# ControlUnit.net
KiCad netlist of a schematic drawn in Altium Designer
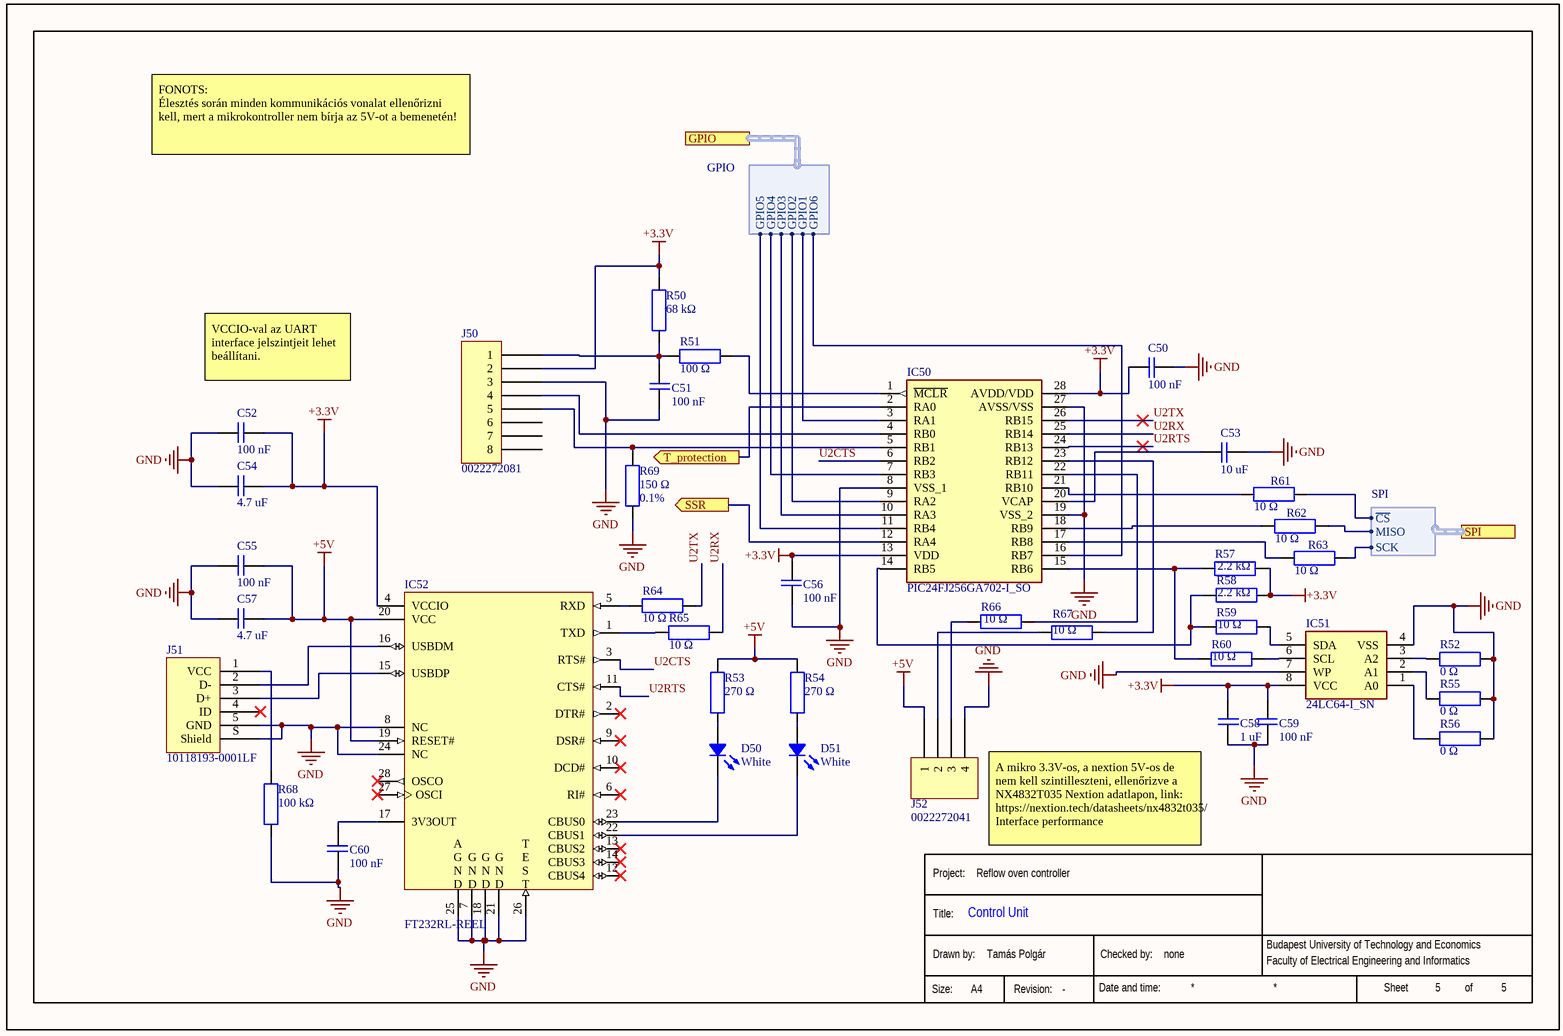
[diagram p0: ControlUnit.SchDoc]

(export (version "E")
  (design (tool "Eeschema 10.0.6"))
  (components
    (comp (ref "C50")
      (value "100 nF")
      (footprint "1206 MLCC")
      (description "Generic MLCC")
      (libsource (lib "passives") (part "Capacitor"))
    )
    (comp (ref "C51")
      (value "100 nF")
      (footprint "1206 MLCC")
      (description "Generic MLCC")
      (libsource (lib "passives") (part "Capacitor"))
    )
    (comp (ref "C52")
      (value "100 nF")
      (footprint "1206 MLCC")
      (description "Generic MLCC")
      (libsource (lib "passives") (part "Capacitor"))
    )
    (comp (ref "C53")
      (value "10 uF")
      (footprint "1210 MLCC")
      (description "Generic MLCC")
      (libsource (lib "passives") (part "Capacitor"))
    )
    (comp (ref "C54")
      (value "4.7 uF")
      (footprint "1206 MLCC")
      (description "Generic MLCC")
      (libsource (lib "passives") (part "Capacitor"))
    )
    (comp (ref "C55")
      (value "100 nF")
      (footprint "1206 MLCC")
      (description "Generic MLCC")
      (libsource (lib "passives") (part "Capacitor"))
    )
    (comp (ref "C56")
      (value "100 nF")
      (footprint "1206 MLCC")
      (description "Generic MLCC")
      (libsource (lib "passives") (part "Capacitor"))
    )
    (comp (ref "C57")
      (value "4.7 uF")
      (footprint "1206 MLCC")
      (description "Generic MLCC")
      (libsource (lib "passives") (part "Capacitor"))
    )
    (comp (ref "C58")
      (value "1 uF")
      (footprint "1206 MLCC")
      (description "Generic MLCC")
      (libsource (lib "passives") (part "Capacitor"))
    )
    (comp (ref "C59")
      (value "100 nF")
      (footprint "1206 MLCC")
      (description "Generic MLCC")
      (libsource (lib "passives") (part "Capacitor"))
    )
    (comp (ref "C60")
      (value "100 nF")
      (footprint "1206 MLCC")
      (description "Generic MLCC")
      (libsource (lib "passives") (part "Capacitor"))
    )
    (comp (ref "D50")
      (value "White")
      (footprint "LED 1206_3216")
      (description "LED WHITE 1206 SMD")
      (fields (field (name "PART NUMBER") "LTW-C230DS") (field (name "MANUFACTURER") "Lite-On Inc."))
      (libsource (lib "Celestial Altium Library - altium_library") (part "LED"))
    )
    (comp (ref "D51")
      (value "White")
      (footprint "LED 1206_3216")
      (description "LED WHITE 1206 SMD")
      (fields (field (name "PART NUMBER") "LTW-C230DS") (field (name "MANUFACTURER") "Lite-On Inc."))
      (libsource (lib "Celestial Altium Library - altium_library") (part "LED"))
    )
    (comp (ref "IC50")
      (value "PIC24FJ256GA702-I_SO")
      (footprint "SamacSys:SOIC127P1030X265-28N")
      (description "Integrated Circuit")
      (fields
        (field (name "MANUFACTURER_PART_NUMBER") "PIC24FJ256GA702-I/SO")
        (field (name "MOUSER PART NUMBER") "579-24FJ256GA702ISO")
      )
      (libsource (lib "*") (part "PIC24FJ256GA702-I_SO"))
    )
    (comp (ref "IC51")
      (value "24LC64-I_SN")
      (footprint "SamacSys:SOIC127P600X175-8N")
      (description "Integrated Circuit")
      (fields
        (field (name "MANUFACTURER_PART_NUMBER") "24LC64-I/SN")
        (field (name "MOUSER PART NUMBER") "579-24LC64-I/SN")
      )
      (libsource (lib "*") (part "24LC64-I_SN"))
    )
    (comp (ref "IC52")
      (value "FT232RL-REEL")
      (footprint "FTDI-SSOP-28_N")
      (description "USB UART IC, -0.5 to 6 V, 24 mA, -40 to 85 degC, 28-Pin SSOP, RoHS, Tape and Reel")
      (fields (field (name "MANUFACTURER") "Future Technology Devices International (FTDI)"))
      (libsource (lib "Budapest University of Technology and Economics") (part "FTDI-FT232-SSOP-28"))
    )
    (comp (ref "J50")
      (value "0022272081")
      (footprint "MOLEX KK 0022272081")
      (description "CONN HEADER VERT 8POS 2.54MM")
      (fields (field (name "MANUFACTURER") "Molex"))
      (libsource (lib "Celestial Altium Library - altium_library") (part "8 Pin"))
    )
    (comp (ref "J51")
      (value "10118193-0001LF")
      (footprint "FCI USB 10118193-0001LF")
      (description "CONN RCPT USB2.0 MICRO B SMD R/A")
      (fields (field (name "MANUFACTURER") "Amphenol ICC (FCI)"))
      (libsource (lib "Celestial Altium Library - altium_library") (part "USB 2.0 Type B Micro"))
    )
    (comp (ref "J52")
      (value "0022272041")
      (footprint "MOLEX KK 0022272041")
      (description "CONN HEADER VERT 4POS 2.54MM")
      (fields (field (name "MANUFACTURER") "Molex"))
      (libsource (lib "Celestial Altium Library - altium_library") (part "4 Pin"))
    )
    (comp (ref "R50")
      (value "68 kΩ")
      (footprint "1206 RES")
      (description "Generic SMD resistor")
      (libsource (lib "") (part "Resitor_1"))
    )
    (comp (ref "R51")
      (value "100 Ω")
      (footprint "1206 RES")
      (description "Generic SMD resistor")
      (libsource (lib "passives") (part "Resitor"))
    )
    (comp (ref "R52")
      (value "0 Ω")
      (footprint "1206 RES")
      (description "Generic SMD resistor")
      (libsource (lib "passives") (part "Resitor"))
    )
    (comp (ref "R53")
      (value "270 Ω")
      (footprint "1206 RES")
      (description "Generic SMD resistor")
      (libsource (lib "") (part "Resitor_1"))
    )
    (comp (ref "R54")
      (value "270 Ω")
      (footprint "1206 RES")
      (description "Generic SMD resistor")
      (libsource (lib "") (part "Resitor_2"))
    )
    (comp (ref "R55")
      (value "0 Ω")
      (footprint "1206 RES")
      (description "Generic SMD resistor")
      (libsource (lib "passives") (part "Resitor"))
    )
    (comp (ref "R56")
      (value "0 Ω")
      (footprint "1206 RES")
      (description "Generic SMD resistor")
      (libsource (lib "passives") (part "Resitor"))
    )
    (comp (ref "R57")
      (value "2.2 kΩ")
      (footprint "1206 RES")
      (description "Generic SMD resistor")
      (libsource (lib "passives") (part "Resitor"))
    )
    (comp (ref "R58")
      (value "2.2 kΩ")
      (footprint "1206 RES")
      (description "Generic SMD resistor")
      (libsource (lib "passives") (part "Resitor"))
    )
    (comp (ref "R59")
      (value "10 Ω")
      (footprint "1206 RES")
      (description "Generic SMD resistor")
      (libsource (lib "passives") (part "Resitor"))
    )
    (comp (ref "R60")
      (value "10 Ω")
      (footprint "1206 RES")
      (description "Generic SMD resistor")
      (libsource (lib "passives") (part "Resitor"))
    )
    (comp (ref "R61")
      (value "10 Ω")
      (footprint "1206 RES")
      (description "Generic SMD resistor")
      (libsource (lib "passives") (part "Resitor"))
    )
    (comp (ref "R62")
      (value "10 Ω")
      (footprint "1206 RES")
      (description "Generic SMD resistor")
      (libsource (lib "passives") (part "Resitor"))
    )
    (comp (ref "R63")
      (value "10 Ω")
      (footprint "1206 RES")
      (description "Generic SMD resistor")
      (libsource (lib "passives") (part "Resitor"))
    )
    (comp (ref "R64")
      (value "10 Ω")
      (footprint "1206 RES")
      (description "Generic SMD resistor")
      (libsource (lib "passives") (part "Resitor"))
    )
    (comp (ref "R65")
      (value "10 Ω")
      (footprint "1206 RES")
      (description "Generic SMD resistor")
      (libsource (lib "passives") (part "Resitor"))
    )
    (comp (ref "R66")
      (value "10 Ω")
      (footprint "1206 RES")
      (description "Generic SMD resistor")
      (libsource (lib "passives") (part "Resitor"))
    )
    (comp (ref "R67")
      (value "10 Ω")
      (footprint "1206 RES")
      (description "Generic SMD resistor")
      (libsource (lib "passives") (part "Resitor"))
    )
    (comp (ref "R68")
      (value "100 kΩ")
      (footprint "0805 RES")
      (description "Generic SMD resistor")
      (libsource (lib "") (part "Resitor_1"))
    )
    (comp (ref "R69")
      (value "150 Ω")
      (footprint "1206 RES")
      (description "Precision SMD resistor")
      (fields (field (name "TPYE") "0.1%"))
      (libsource (lib "") (part "Resitor_1"))
    )
  )
  (nets
    (net (code "3") (name "+3.3V") (class "Default")
      (node (ref "C50") (pin "2") (pintype "passive"))
      (node (ref "C52") (pin "2") (pintype "passive"))
      (node (ref "C54") (pin "2") (pintype "passive"))
      (node (ref "C56") (pin "2") (pintype "passive"))
      (node (ref "C58") (pin "1") (pintype "passive"))
      (node (ref "C59") (pin "2") (pintype "passive"))
      (node (ref "IC50") (pin "13") (pinfunction "VDD_13") (pintype "passive"))
      (node (ref "IC50") (pin "28") (pinfunction "AVDD/VDD_28") (pintype "passive"))
      (node (ref "IC51") (pin "8") (pinfunction "VCC_8") (pintype "passive"))
      (node (ref "IC52") (pin "4") (pinfunction "VCCIO_4") (pintype "power_in"))
      (node (ref "J50") (pin "2") (pinfunction "2_2") (pintype "passive"))
      (node (ref "R50") (pin "1") (pintype "passive"))
      (node (ref "R57") (pin "1") (pintype "passive"))
      (node (ref "R58") (pin "1") (pintype "passive"))
    )
    (net (code "4") (name "+5V") (class "Default")
      (node (ref "C55") (pin "2") (pintype "passive"))
      (node (ref "C57") (pin "2") (pintype "passive"))
      (node (ref "IC52") (pin "19") (pinfunction "RESET#_19") (pintype "input"))
      (node (ref "IC52") (pin "20") (pinfunction "VCC_20") (pintype "power_in"))
      (node (ref "J52") (pin "1") (pinfunction "1_1") (pintype "passive"))
      (node (ref "R53") (pin "1") (pintype "passive"))
      (node (ref "R54") (pin "2") (pintype "passive"))
    )
    (net (code "5") (name "/GPIO1") (class "Default")
      (node (ref "IC50") (pin "3") (pinfunction "RA1_3") (pintype "passive"))
    )
    (net (code "6") (name "/GPIO2") (class "Default")
      (node (ref "IC50") (pin "9") (pinfunction "RA2_9") (pintype "passive"))
    )
    (net (code "7") (name "/GPIO3") (class "Default")
      (node (ref "IC50") (pin "10") (pinfunction "RA3_10") (pintype "passive"))
    )
    (net (code "8") (name "/GPIO4") (class "Default")
      (node (ref "IC50") (pin "7") (pinfunction "RB3_7") (pintype "passive"))
    )
    (net (code "9") (name "/GPIO5") (class "Default")
      (node (ref "IC50") (pin "11") (pinfunction "RB4_11") (pintype "passive"))
    )
    (net (code "10") (name "/GPIO6") (class "Default")
      (node (ref "IC50") (pin "16") (pinfunction "RB7_16") (pintype "passive"))
    )
    (net (code "11") (name "/MISO") (class "Default") (node (ref "R62") (pin "1") (pintype "passive")))
    (net (code "12") (name "/SCK") (class "Default") (node (ref "R63") (pin "1") (pintype "passive")))
    (net (code "13") (name "/SSR") (class "Default")
      (node (ref "IC50") (pin "12") (pinfunction "RA4_12") (pintype "passive"))
    )
    (net (code "14") (name "/T_protection") (class "Default")
      (node (ref "IC50") (pin "2") (pinfunction "RA0_2") (pintype "passive"))
    )
    (net (code "15") (name "/U2CTS") (class "Default")
      (node (ref "IC50") (pin "6") (pinfunction "RB2_6") (pintype "passive"))
      (node (ref "IC52") (pin "3") (pinfunction "RTS#_3") (pintype "output"))
    )
    (net (code "16") (name "/U2RTS") (class "Default")
      (node (ref "IC50") (pin "24") (pinfunction "RB13_24") (pintype "passive"))
      (node (ref "IC52") (pin "11") (pinfunction "CTS#_11") (pintype "input"))
    )
    (net (code "17") (name "/U2RX") (class "Default")
      (node (ref "IC50") (pin "25") (pinfunction "RB14_25") (pintype "passive"))
      (node (ref "R65") (pin "1") (pintype "passive"))
    )
    (net (code "18") (name "/U2TX") (class "Default")
      (node (ref "IC50") (pin "26") (pinfunction "RB15_26") (pintype "passive"))
      (node (ref "R64") (pin "1") (pintype "passive"))
    )
    (net (code "21") (name "/~{CS}") (class "Default") (node (ref "R61") (pin "1") (pintype "passive")))
    (net (code "22") (name "GND") (class "Default")
      (node (ref "C50") (pin "1") (pintype "passive"))
      (node (ref "C51") (pin "2") (pintype "passive"))
      (node (ref "C52") (pin "1") (pintype "passive"))
      (node (ref "C53") (pin "1") (pintype "passive"))
      (node (ref "C54") (pin "1") (pintype "passive"))
      (node (ref "C55") (pin "1") (pintype "passive"))
      (node (ref "C56") (pin "1") (pintype "passive"))
      (node (ref "C57") (pin "1") (pintype "passive"))
      (node (ref "C58") (pin "2") (pintype "passive"))
      (node (ref "C59") (pin "1") (pintype "passive"))
      (node (ref "C60") (pin "1") (pintype "passive"))
      (node (ref "IC50") (pin "19") (pinfunction "VSS_2_19") (pintype "passive"))
      (node (ref "IC50") (pin "27") (pinfunction "AVSS/VSS_27") (pintype "passive"))
      (node (ref "IC50") (pin "8") (pinfunction "VSS_1_8") (pintype "passive"))
      (node (ref "IC51") (pin "4") (pinfunction "VSS_4") (pintype "passive"))
      (node (ref "IC51") (pin "7") (pinfunction "WP_7") (pintype "passive"))
      (node (ref "IC52") (pin "18") (pinfunction "GND_18") (pintype "power_in"))
      (node (ref "IC52") (pin "21") (pinfunction "GND_21") (pintype "power_in"))
      (node (ref "IC52") (pin "24") (pinfunction "NC_24") (pintype "passive"))
      (node (ref "IC52") (pin "25") (pinfunction "AGND_25") (pintype "power_in"))
      (node (ref "IC52") (pin "26") (pinfunction "TEST_26") (pintype "input"))
      (node (ref "IC52") (pin "7") (pinfunction "GND_7") (pintype "power_in"))
      (node (ref "IC52") (pin "8") (pinfunction "NC_8") (pintype "passive"))
      (node (ref "J50") (pin "3") (pinfunction "3_3") (pintype "passive"))
      (node (ref "J51") (pin "5") (pinfunction "GND_5") (pintype "passive"))
      (node (ref "J51") (pin "S") (pinfunction "Shield_S") (pintype "passive"))
      (node (ref "J52") (pin "4") (pinfunction "4_4") (pintype "passive"))
      (node (ref "R52") (pin "1") (pintype "passive"))
      (node (ref "R55") (pin "1") (pintype "passive"))
      (node (ref "R56") (pin "1") (pintype "passive"))
      (node (ref "R68") (pin "2") (pintype "passive"))
      (node (ref "R69") (pin "2") (pintype "passive"))
    )
    (net (code "23") (name "Net-(C51-Pad1)") (class "Default")
      (node (ref "C51") (pin "1") (pintype "passive"))
      (node (ref "J50") (pin "1") (pinfunction "1_1") (pintype "passive"))
      (node (ref "R50") (pin "2") (pintype "passive"))
      (node (ref "R51") (pin "2") (pintype "passive"))
    )
    (net (code "24") (name "Net-(D50-Pad1)") (class "Default")
      (node (ref "D50") (pin "1") (pinfunction "1_1") (pintype "passive"))
      (node (ref "R53") (pin "2") (pintype "passive"))
    )
    (net (code "25") (name "Net-(D51-Pad1)") (class "Default")
      (node (ref "D51") (pin "1") (pinfunction "1_1") (pintype "passive"))
      (node (ref "R54") (pin "1") (pintype "passive"))
    )
    (net (code "26") (name "Net-(IC50-RB0)") (class "Default")
      (node (ref "IC50") (pin "4") (pinfunction "RB0_4") (pintype "passive"))
      (node (ref "J50") (pin "4") (pinfunction "4_4") (pintype "passive"))
    )
    (net (code "27") (name "Net-(IC50-RB1)") (class "Default")
      (node (ref "IC50") (pin "5") (pinfunction "RB1_5") (pintype "passive"))
      (node (ref "J50") (pin "5") (pinfunction "5_5") (pintype "passive"))
      (node (ref "R69") (pin "1") (pintype "passive"))
    )
    (net (code "28") (name "Net-(IC50-RB5)") (class "Default")
      (node (ref "IC50") (pin "14") (pinfunction "RB5_14") (pintype "passive"))
      (node (ref "R58") (pin "2") (pintype "passive"))
      (node (ref "R59") (pin "2") (pintype "passive"))
    )
    (net (code "29") (name "Net-(IC50-RB6)") (class "Default")
      (node (ref "IC50") (pin "15") (pinfunction "RB6_15") (pintype "passive"))
      (node (ref "R57") (pin "2") (pintype "passive"))
      (node (ref "R60") (pin "2") (pintype "passive"))
    )
    (net (code "30") (name "Net-(IC50-RB8)") (class "Default")
      (node (ref "IC50") (pin "17") (pinfunction "RB8_17") (pintype "passive"))
      (node (ref "R63") (pin "2") (pintype "passive"))
    )
    (net (code "31") (name "Net-(IC50-RB9)") (class "Default")
      (node (ref "IC50") (pin "18") (pinfunction "RB9_18") (pintype "passive"))
      (node (ref "R62") (pin "2") (pintype "passive"))
    )
    (net (code "32") (name "Net-(IC50-RB10)") (class "Default")
      (node (ref "IC50") (pin "21") (pinfunction "RB10_21") (pintype "passive"))
      (node (ref "R61") (pin "2") (pintype "passive"))
    )
    (net (code "33") (name "Net-(IC50-RB11)") (class "Default")
      (node (ref "IC50") (pin "22") (pinfunction "RB11_22") (pintype "passive"))
      (node (ref "R66") (pin "1") (pintype "passive"))
    )
    (net (code "34") (name "Net-(IC50-RB12)") (class "Default")
      (node (ref "IC50") (pin "23") (pinfunction "RB12_23") (pintype "passive"))
      (node (ref "R67") (pin "1") (pintype "passive"))
    )
    (net (code "35") (name "Net-(IC50-VCAP)") (class "Default")
      (node (ref "C53") (pin "2") (pintype "passive"))
      (node (ref "IC50") (pin "20") (pinfunction "VCAP_20") (pintype "passive"))
    )
    (net (code "36") (name "Net-(IC50-~{MCLR})") (class "Default")
      (node (ref "IC50") (pin "1") (pinfunction "~{MCLR}_1") (pintype "output"))
      (node (ref "R51") (pin "1") (pintype "passive"))
    )
    (net (code "37") (name "Net-(IC51-A0)") (class "Default")
      (node (ref "IC51") (pin "1") (pinfunction "A0_1") (pintype "passive"))
      (node (ref "R56") (pin "2") (pintype "passive"))
    )
    (net (code "38") (name "Net-(IC51-A1)") (class "Default")
      (node (ref "IC51") (pin "2") (pinfunction "A1_2") (pintype "passive"))
      (node (ref "R55") (pin "2") (pintype "passive"))
    )
    (net (code "39") (name "Net-(IC51-A2)") (class "Default")
      (node (ref "IC51") (pin "3") (pinfunction "A2_3") (pintype "passive"))
      (node (ref "R52") (pin "2") (pintype "passive"))
    )
    (net (code "40") (name "Net-(IC51-SCL)") (class "Default")
      (node (ref "IC51") (pin "6") (pinfunction "SCL_6") (pintype "passive"))
      (node (ref "R60") (pin "1") (pintype "passive"))
    )
    (net (code "41") (name "Net-(IC51-SDA)") (class "Default")
      (node (ref "IC51") (pin "5") (pinfunction "SDA_5") (pintype "passive"))
      (node (ref "R59") (pin "1") (pintype "passive"))
    )
    (net (code "42") (name "Net-(IC52-3V3OUT)") (class "Default")
      (node (ref "C60") (pin "2") (pintype "passive"))
      (node (ref "IC52") (pin "17") (pinfunction "3V3OUT_17") (pintype "power_in"))
    )
    (net (code "43") (name "Net-(IC52-CBUS0)") (class "Default")
      (node (ref "D50") (pin "2") (pinfunction "2_2") (pintype "passive"))
      (node (ref "IC52") (pin "23") (pinfunction "CBUS0_23") (pintype "bidirectional"))
    )
    (net (code "44") (name "Net-(IC52-CBUS1)") (class "Default")
      (node (ref "D51") (pin "2") (pinfunction "2_2") (pintype "passive"))
      (node (ref "IC52") (pin "22") (pinfunction "CBUS1_22") (pintype "bidirectional"))
    )
    (net (code "45") (name "Net-(IC52-RXD)") (class "Default")
      (node (ref "IC52") (pin "5") (pinfunction "RXD_5") (pintype "input"))
      (node (ref "R64") (pin "2") (pintype "passive"))
    )
    (net (code "46") (name "Net-(IC52-TXD)") (class "Default")
      (node (ref "IC52") (pin "1") (pinfunction "TXD_1") (pintype "output"))
      (node (ref "R65") (pin "2") (pintype "passive"))
    )
    (net (code "47") (name "Net-(IC52-USBDM)") (class "Default")
      (node (ref "IC52") (pin "16") (pinfunction "USBDM_16") (pintype "bidirectional"))
      (node (ref "J51") (pin "2") (pinfunction "D-_2") (pintype "passive"))
    )
    (net (code "48") (name "Net-(IC52-USBDP)") (class "Default")
      (node (ref "IC52") (pin "15") (pinfunction "USBDP_15") (pintype "bidirectional"))
      (node (ref "J51") (pin "3") (pinfunction "D+_3") (pintype "passive"))
    )
    (net (code "49") (name "Net-(J51-VCC)") (class "Default")
      (node (ref "J51") (pin "1") (pinfunction "VCC_1") (pintype "passive"))
      (node (ref "R68") (pin "1") (pintype "passive"))
    )
    (net (code "50") (name "Net-(J52-Pad2)") (class "Default")
      (node (ref "J52") (pin "2") (pinfunction "2_2") (pintype "passive"))
      (node (ref "R67") (pin "2") (pintype "passive"))
    )
    (net (code "51") (name "Net-(J52-Pad3)") (class "Default")
      (node (ref "J52") (pin "3") (pinfunction "3_3") (pintype "passive"))
      (node (ref "R66") (pin "2") (pintype "passive"))
    )
    (net (code "52") (name "unconnected-(IC52-CBUS2-Pad13)") (class "Default")
      (node (ref "IC52") (pin "13") (pinfunction "CBUS2_13") (pintype "bidirectional+no_connect"))
    )
    (net (code "53") (name "unconnected-(IC52-CBUS3-Pad14)") (class "Default")
      (node (ref "IC52") (pin "14") (pinfunction "CBUS3_14") (pintype "bidirectional+no_connect"))
    )
    (net (code "54") (name "unconnected-(IC52-CBUS4-Pad12)") (class "Default")
      (node (ref "IC52") (pin "12") (pinfunction "CBUS4_12") (pintype "bidirectional+no_connect"))
    )
    (net (code "55") (name "unconnected-(IC52-DCD#-Pad10)") (class "Default")
      (node (ref "IC52") (pin "10") (pinfunction "DCD#_10") (pintype "input+no_connect"))
    )
    (net (code "56") (name "unconnected-(IC52-DSR#-Pad9)") (class "Default")
      (node (ref "IC52") (pin "9") (pinfunction "DSR#_9") (pintype "input+no_connect"))
    )
    (net (code "57") (name "unconnected-(IC52-DTR#-Pad2)") (class "Default")
      (node (ref "IC52") (pin "2") (pinfunction "DTR#_2") (pintype "output+no_connect"))
    )
    (net (code "58") (name "unconnected-(IC52-OSCI-Pad27)") (class "Default")
      (node (ref "IC52") (pin "27") (pinfunction "OSCI_27") (pintype "input+no_connect"))
    )
    (net (code "59") (name "unconnected-(IC52-OSCO-Pad28)") (class "Default")
      (node (ref "IC52") (pin "28") (pinfunction "OSCO_28") (pintype "output+no_connect"))
    )
    (net (code "60") (name "unconnected-(IC52-RI#-Pad6)") (class "Default")
      (node (ref "IC52") (pin "6") (pinfunction "RI#_6") (pintype "input+no_connect"))
    )
    (net (code "61") (name "unconnected-(J50-Pad6)") (class "Default")
      (node (ref "J50") (pin "6") (pinfunction "6_6") (pintype "passive"))
    )
    (net (code "62") (name "unconnected-(J50-Pad7)") (class "Default")
      (node (ref "J50") (pin "7") (pinfunction "7_7") (pintype "passive"))
    )
    (net (code "63") (name "unconnected-(J50-Pad8)") (class "Default")
      (node (ref "J50") (pin "8") (pinfunction "8_8") (pintype "passive"))
    )
    (net (code "64") (name "unconnected-(J51-ID-Pad4)") (class "Default")
      (node (ref "J51") (pin "4") (pinfunction "ID_4") (pintype "passive+no_connect"))
    )
  )
)
